# MP4GS_Power.net
KiCad netlist of a schematic drawn in EAGLE
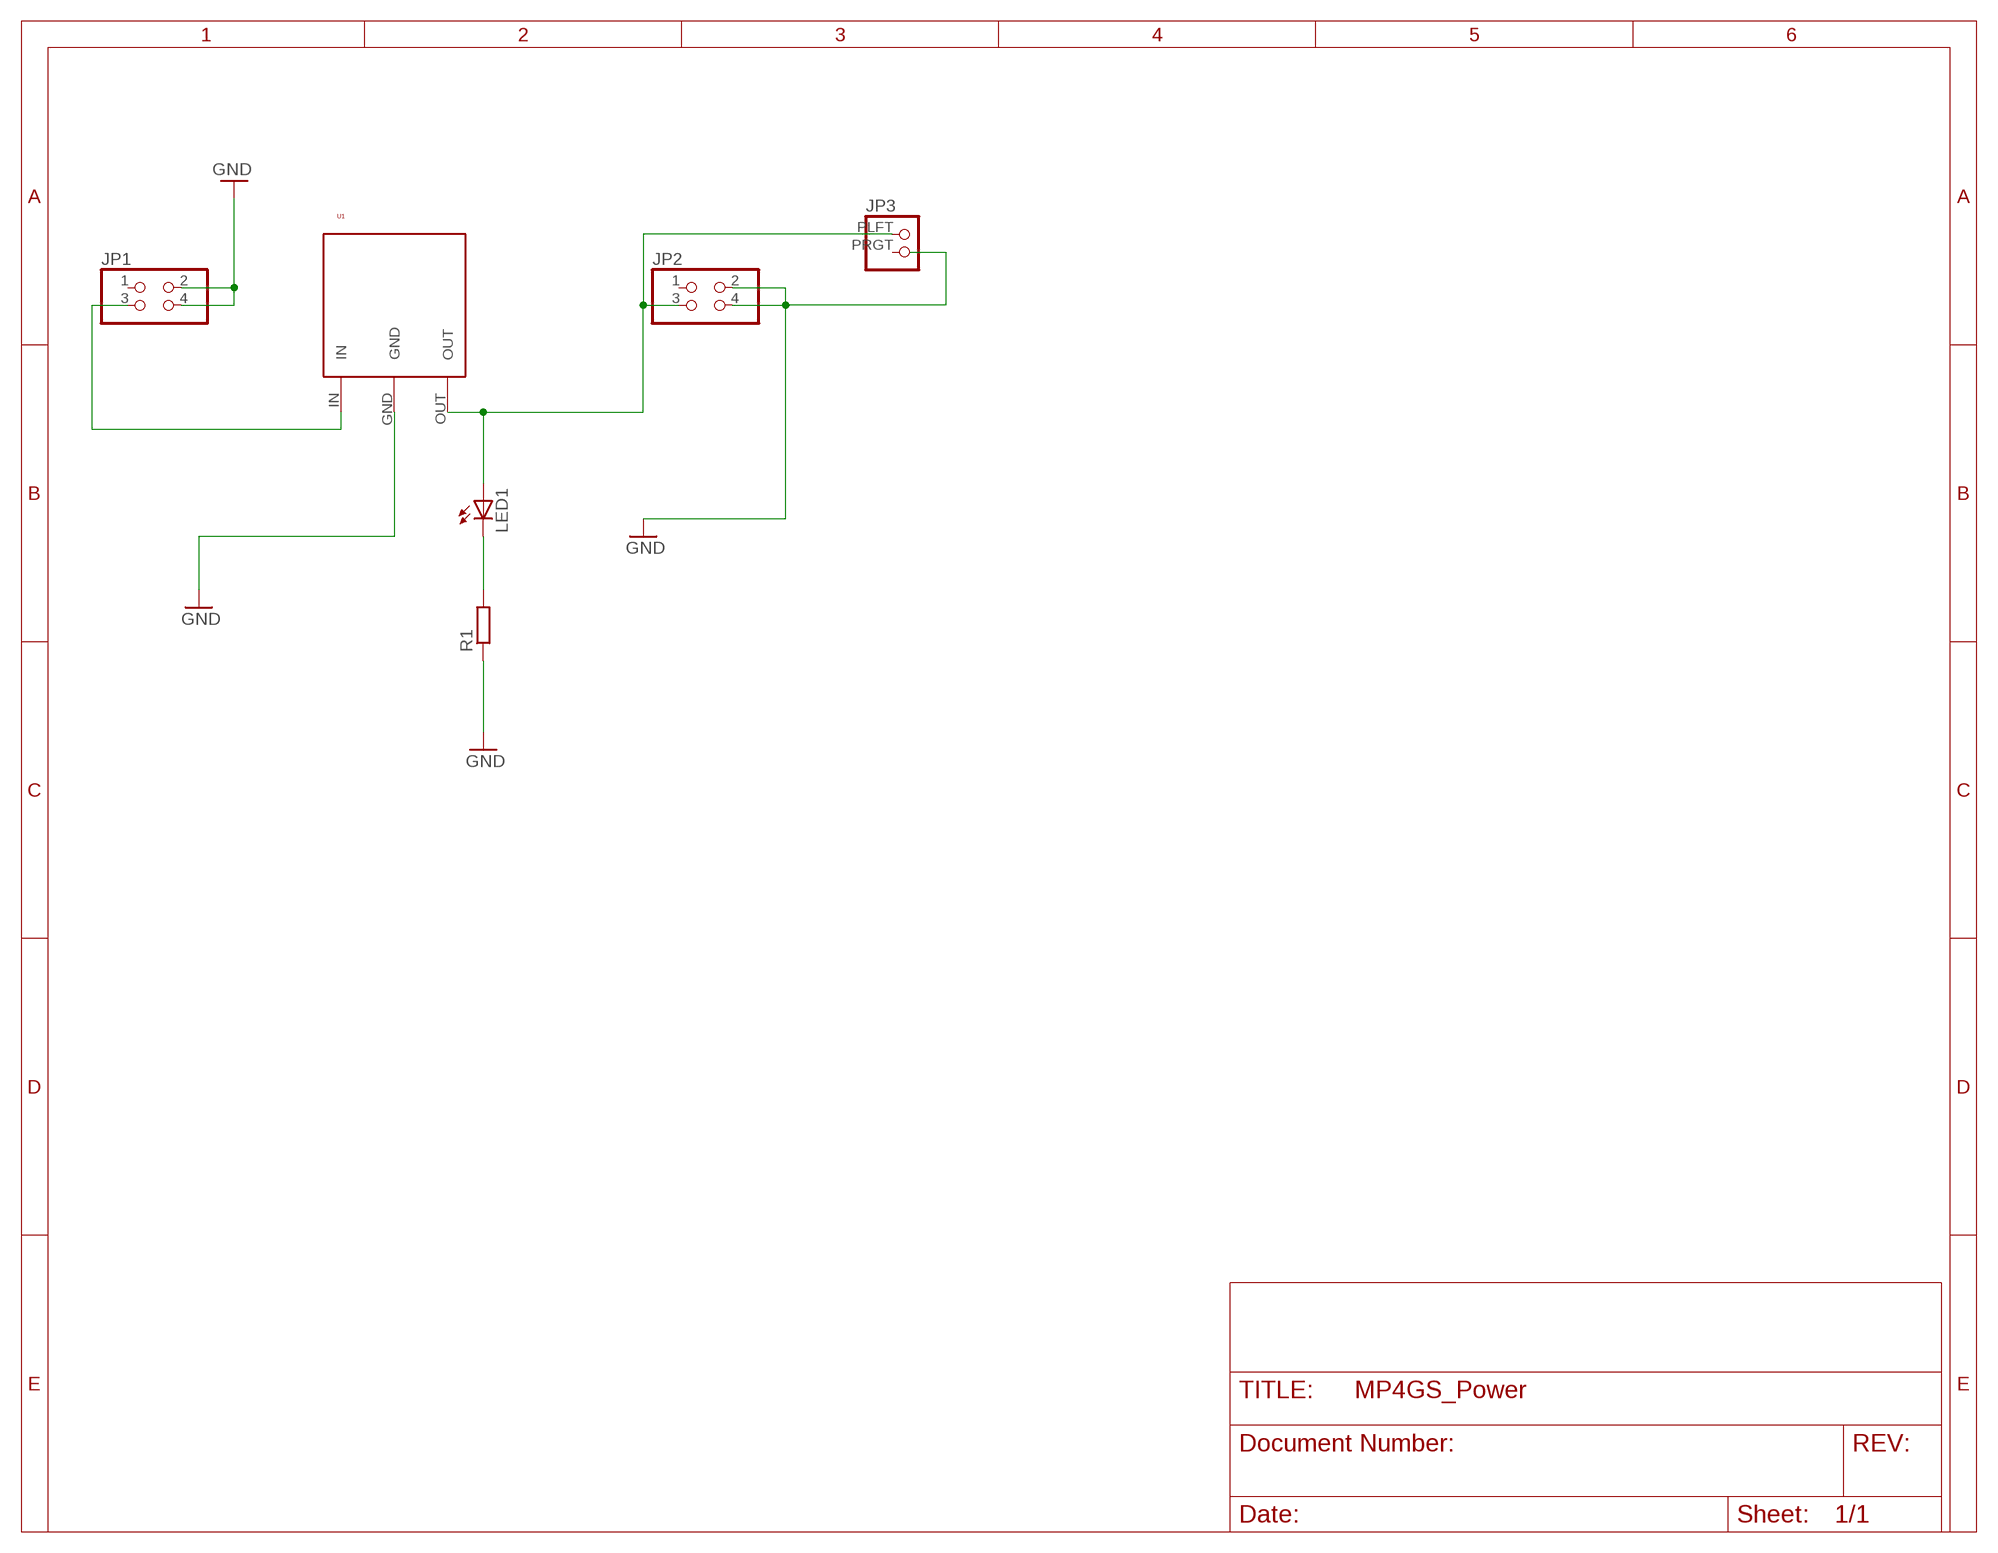
[diagram p0: schematic, sheet 1]

(export (version "E")
  (design (tool "Eeschema 10.0.6"))
  (components
    (comp (ref "JP1")
      (value "PINHD-2X2")
      (footprint "eagle-import:2X02")
      (libsource (lib "eagle-import") (part "PINHD-2X2"))
    )
    (comp (ref "JP2")
      (value "PINHD-2X2")
      (footprint "eagle-import:2X02")
      (libsource (lib "eagle-import") (part "PINHD-2X2"))
    )
    (comp (ref "JP3")
      (value "PINHD-1X2")
      (footprint "eagle-import:1X02")
      (libsource (lib "eagle-import") (part "PINHD-1X2"))
    )
    (comp (ref "LED1")
      (value "LED5MM")
      (footprint "eagle-import:LED5MM")
      (libsource (lib "eagle-import") (part "LED5MM"))
    )
    (comp (ref "R1")
      (value "R-EU_0207/10")
      (footprint "eagle-import:0207_10")
      (libsource (lib "eagle-import") (part "R-EU_0207/10"))
    )
    (comp (ref "U1")
      (value "L7808AB")
      (footprint "eagle-import:L78-DDPAK")
      (libsource (lib "eagle-import") (part "L7808AB"))
    )
  )
  (nets
    (net (code "1") (name "GND") (class "Default")
      (node (ref "JP1") (pin "2") (pinfunction "2_2") (pintype "passive"))
      (node (ref "JP1") (pin "4") (pinfunction "4_4") (pintype "passive"))
      (node (ref "JP2") (pin "2") (pinfunction "2_2") (pintype "passive"))
      (node (ref "JP2") (pin "4") (pinfunction "4_4") (pintype "passive"))
      (node (ref "R1") (pin "1") (pinfunction "1_1") (pintype "passive"))
      (node (ref "U1") (pin "GND") (pinfunction "GND_GND") (pintype "power_in"))
    )
    (net (code "2") (name "Net-(JP1-Pad3)") (class "Default")
      (node (ref "JP1") (pin "3") (pinfunction "3_3") (pintype "passive"))
      (node (ref "U1") (pin "IN") (pinfunction "IN_IN") (pintype "input"))
    )
    (net (code "3") (name "Net-(JP3-1)") (class "Default")
      (node (ref "JP2") (pin "3") (pinfunction "3_3") (pintype "passive"))
      (node (ref "JP3") (pin "PLFT") (pinfunction "1_PLFT") (pintype "passive"))
      (node (ref "LED1") (pin "A") (pinfunction "A_A") (pintype "passive"))
      (node (ref "U1") (pin "OUT") (pinfunction "OUT_OUT") (pintype "output"))
    )
    (net (code "4") (name "Net-(LED1-C)") (class "Default")
      (node (ref "LED1") (pin "K") (pinfunction "C_K") (pintype "passive"))
      (node (ref "R1") (pin "2") (pinfunction "2_2") (pintype "passive"))
    )
    (net (code "5") (name "unconnected-(JP1-Pad1)") (class "Default")
      (node (ref "JP1") (pin "1") (pinfunction "1_1") (pintype "passive"))
    )
    (net (code "6") (name "unconnected-(JP2-Pad1)") (class "Default")
      (node (ref "JP2") (pin "1") (pinfunction "1_1") (pintype "passive"))
    )
    (net (code "7") (name "unconnected-(JP3-2-PadPRGT)") (class "Default")
      (node (ref "JP3") (pin "PRGT") (pinfunction "2_PRGT") (pintype "passive"))
    )
  )
)
